# IO.net
KiCad netlist of a schematic drawn in Altium Designer
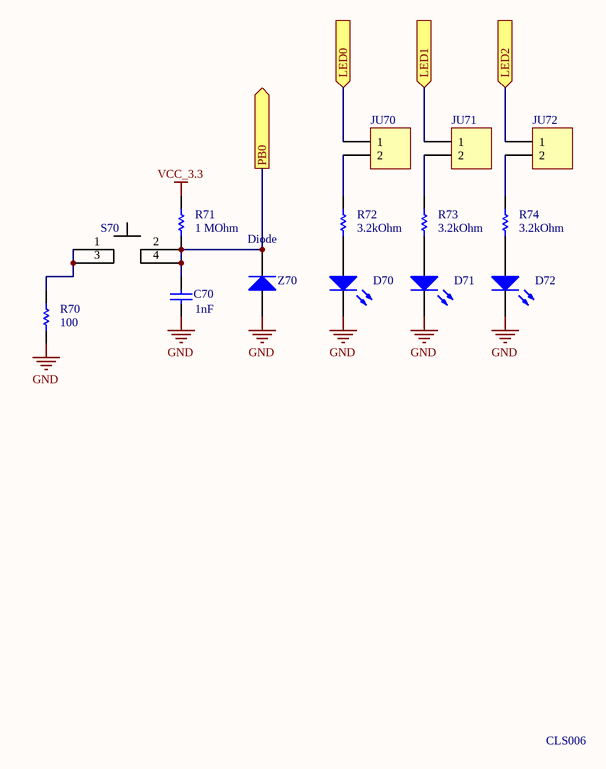
[diagram p0: IO.SchDoc]

(export (version "E")
  (design (tool "Eeschema 10.0.6"))
  (components
    (comp (ref "C70")
      (value "1nF")
      (footprint "0805_CHIP_FP")
      (fields
        (field (name "MANUFACTURER") "Johanson Dielectrics Inc.")
        (field (name "MANUFACTURER PART NUMBER") "500R15N102JV4T")
        (field (name "VENDOR PART NUMBER") "709-1180-1-ND")
      )
      (libsource (lib "GenericSymbols") (part "Capacitor_unpolarized_0603"))
    )
    (comp (ref "D70")
      (value "LED Generic")
      (footprint "LED_FP")
      (fields
        (field (name "MANUFACTURER") "Broadcom Limited")
        (field (name "MANUFACTURER PART NUMBER") "HLMP-P156-HK011")
        (field (name "VENDOR PART NUMBER") "516-4089-1-ND")
      )
      (libsource (lib "GenericSymbols") (part "LED_generic"))
    )
    (comp (ref "D71")
      (value "LED Generic")
      (footprint "LED_FP")
      (description "LED RED CLEAR FLAT 2SMD GW")
      (fields
        (field (name "MANUFACTURER") "Broadcom Limited")
        (field (name "MANUFACTURER PART NUMBER") "HLMP-P156-HK011")
      )
      (libsource (lib "GenericSymbols") (part "LED_generic"))
    )
    (comp (ref "D72")
      (value "LED Generic")
      (footprint "LED_FP")
      (description "LED RED CLEAR FLAT 2SMD GW")
      (fields
        (field (name "MANUFACTURER") "Broadcom Limited")
        (field (name "MANUFACTURER PART NUMBER") "HLMP-P156-HK011")
      )
      (libsource (lib "GenericSymbols") (part "LED_generic"))
    )
    (comp (ref "JU70")
      (value "Header 2")
      (footprint "HDR1X2")
      (description "CONN HEADER .100 SINGL STR 36POS")
      (fields (field (name "VENDOR PART NUMBER") "PRT-00116"))
      (libsource (lib "Miscellaneous Connectors") (part "Header 2"))
    )
    (comp (ref "JU71")
      (value "Header 2")
      (footprint "HDR1X2")
      (description "CONN HEADER .100 SINGL STR 36POS")
      (fields (field (name "VENDOR PART NUMBER") "PRT-00116"))
      (libsource (lib "Miscellaneous Connectors") (part "Header 2"))
    )
    (comp (ref "JU72")
      (value "Header 2")
      (footprint "HDR1X2")
      (description "CONN HEADER .100 SINGL STR 36POS")
      (fields (field (name "VENDOR PART NUMBER") "PRT-00116"))
      (libsource (lib "Miscellaneous Connectors") (part "Header 2"))
    )
    (comp (ref "R70")
      (value "100")
      (footprint "0805_CHIP_FP")
      (fields
        (field (name "MANUFACTURER") "Yageo")
        (field (name "MANUFACTURER PART NUMBER") "RC0805FR-07100RL")
        (field (name "VENDOR PART NUMBER") "311-100CRCT-ND")
      )
      (libsource (lib "GenericSymbols") (part "Resistor_0805"))
    )
    (comp (ref "R71")
      (value "1 MOhm")
      (footprint "0805_CHIP_FP")
      (fields
        (field (name "MANUFACTURER") "Yageo")
        (field (name "MANUFACTURER PART NUMBER") "RC0805FR-071ML")
        (field (name "VENDOR PART NUMBER") "311-1.00MCRCT-ND")
      )
      (libsource (lib "GenericSymbols") (part "Resistor_0805"))
    )
    (comp (ref "R72")
      (value "3.2kOhm")
      (footprint "0805_CHIP_FP")
      (fields
        (field (name "MANUFACTURER") "Yageo")
        (field (name "MANUFACTURER PART NUMBER") "RC0805FR-073K24L")
        (field (name "VENDOR PART NUMBER") "311-3.24KCRCT-ND")
      )
      (libsource (lib "GenericSymbols") (part "Resistor_0805"))
    )
    (comp (ref "R73")
      (value "3.2kOhm")
      (footprint "0805_CHIP_FP")
      (fields
        (field (name "MANUFACTURER") "Yageo")
        (field (name "MANUFACTURER PART NUMBER") "RC0805FR-073K24L")
        (field (name "VENDOR PART NUMBER") "311-3.24KCRCT-ND")
      )
      (libsource (lib "GenericSymbols") (part "Resistor_0805"))
    )
    (comp (ref "R74")
      (value "3.2kOhm")
      (footprint "0805_CHIP_FP")
      (fields
        (field (name "MANUFACTURER") "Yageo")
        (field (name "MANUFACTURER PART NUMBER") "RC0805FR-073K24L")
        (field (name "VENDOR PART NUMBER") "311-3.24KCRCT-ND")
      )
      (libsource (lib "GenericSymbols") (part "Resistor_0805"))
    )
    (comp (ref "S70")
      (value "Switch")
      (footprint "Pushbutton")
      (description "Pushbutton Switch")
      (fields (field (name "MANUFACTURER") "APEM Inc.") (field (name "MANUFACTURER PART NUMBER") "MJTP1230"))
      (libsource (lib "GenericSymbols") (part "Pushbutton"))
    )
    (comp (ref "Z70")
      (value "Diode")
      (footprint "0603_CHIP_FP")
      (description "Default Diode")
      (fields
        (field (name "MANUFACTURER") "STMicroelectronics")
        (field (name "MANUFACTURER PART NUMBER") "ESDA7P120-1U1M")
      )
      (libsource (lib "GenericSymbols") (part "Diode"))
    )
  )
  (nets
    (net (code "1") (name "/LED0") (class "Default")
      (node (ref "JU70") (pin "1") (pinfunction "1_1") (pintype "passive"))
    )
    (net (code "2") (name "/LED1") (class "Default")
      (node (ref "JU71") (pin "1") (pinfunction "1_1") (pintype "passive"))
    )
    (net (code "3") (name "/LED2") (class "Default")
      (node (ref "JU72") (pin "1") (pinfunction "1_1") (pintype "passive"))
    )
    (net (code "4") (name "/PB0") (class "Default")
      (node (ref "C70") (pin "2") (pinfunction "2_2") (pintype "passive"))
      (node (ref "R71") (pin "1") (pinfunction "1_1") (pintype "passive"))
      (node (ref "S70") (pin "2") (pintype "passive"))
      (node (ref "S70") (pin "4") (pintype "passive"))
      (node (ref "Z70") (pin "1") (pinfunction "Anode_1") (pintype "passive"))
    )
    (net (code "5") (name "GND") (class "Default")
      (node (ref "C70") (pin "1") (pinfunction "1_1") (pintype "passive"))
      (node (ref "D70") (pin "2") (pinfunction "K_2") (pintype "passive"))
      (node (ref "D71") (pin "2") (pinfunction "K_2") (pintype "passive"))
      (node (ref "D72") (pin "2") (pinfunction "K_2") (pintype "passive"))
      (node (ref "R70") (pin "1") (pinfunction "1_1") (pintype "passive"))
      (node (ref "Z70") (pin "2") (pinfunction "Cathode_2") (pintype "passive"))
    )
    (net (code "6") (name "Net-(D70-A)") (class "Default")
      (node (ref "D70") (pin "1") (pinfunction "A_1") (pintype "passive"))
      (node (ref "R72") (pin "1") (pinfunction "1_1") (pintype "passive"))
    )
    (net (code "7") (name "Net-(D71-A)") (class "Default")
      (node (ref "D71") (pin "1") (pinfunction "A_1") (pintype "passive"))
      (node (ref "R73") (pin "1") (pinfunction "1_1") (pintype "passive"))
    )
    (net (code "8") (name "Net-(D72-A)") (class "Default")
      (node (ref "D72") (pin "1") (pinfunction "A_1") (pintype "passive"))
      (node (ref "R74") (pin "1") (pinfunction "1_1") (pintype "passive"))
    )
    (net (code "9") (name "Net-(JU70-Pad2)") (class "Default")
      (node (ref "JU70") (pin "2") (pinfunction "2_2") (pintype "passive"))
      (node (ref "R72") (pin "2") (pinfunction "2_2") (pintype "passive"))
    )
    (net (code "10") (name "Net-(JU71-Pad2)") (class "Default")
      (node (ref "JU71") (pin "2") (pinfunction "2_2") (pintype "passive"))
      (node (ref "R73") (pin "2") (pinfunction "2_2") (pintype "passive"))
    )
    (net (code "11") (name "Net-(JU72-Pad2)") (class "Default")
      (node (ref "JU72") (pin "2") (pinfunction "2_2") (pintype "passive"))
      (node (ref "R74") (pin "2") (pinfunction "2_2") (pintype "passive"))
    )
    (net (code "12") (name "Net-(R70-Pad2)") (class "Default")
      (node (ref "R70") (pin "2") (pinfunction "2_2") (pintype "passive"))
      (node (ref "S70") (pin "1") (pintype "passive"))
      (node (ref "S70") (pin "3") (pintype "passive"))
    )
    (net (code "13") (name "VCC_3.3") (class "Default")
      (node (ref "R71") (pin "2") (pinfunction "2_2") (pintype "passive"))
    )
  )
)
